# interface_th.net
KiCad netlist of a schematic drawn in EAGLE
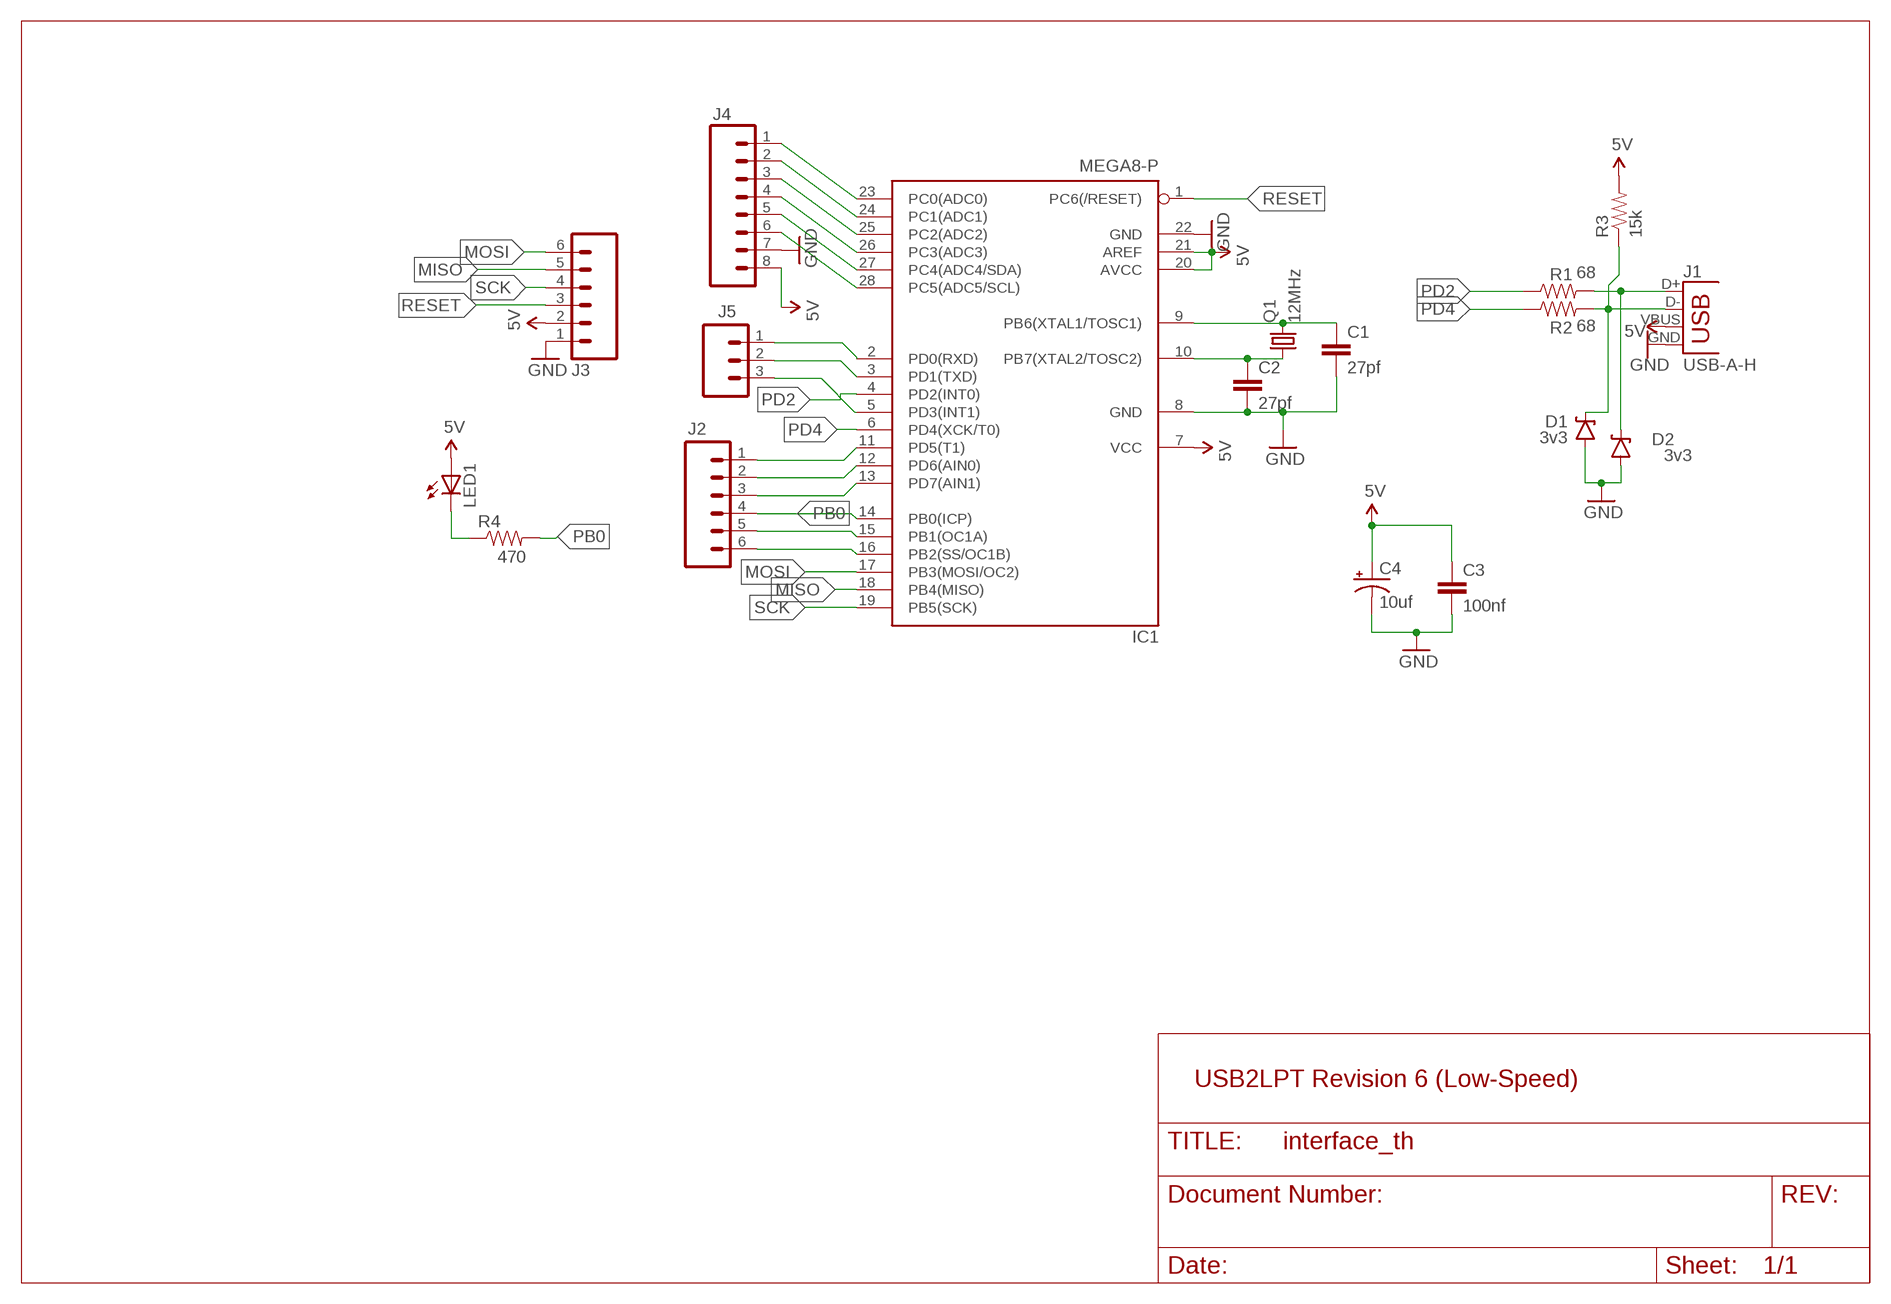
[diagram p0: schematic, sheet 1]

(export (version "E")
  (design (tool "Eeschema 10.0.6"))
  (components
    (comp (ref "C1")
      (value "27pf")
      (footprint "eagle-import:CAP-PTH-SMALL")
      (libsource (lib "eagle-import") (part "SparkFun-Passives_CAPPTH"))
    )
    (comp (ref "C2")
      (value "27pf")
      (footprint "eagle-import:CAP-PTH-SMALL")
      (libsource (lib "eagle-import") (part "SparkFun-Passives_CAPPTH"))
    )
    (comp (ref "C3")
      (value "100nf")
      (footprint "eagle-import:CAP-PTH-SMALL")
      (libsource (lib "eagle-import") (part "CAPPTH"))
    )
    (comp (ref "C4")
      (value "10uf")
      (footprint "eagle-import:CPOL-RADIAL-10UF-25V")
      (libsource (lib "eagle-import") (part "CAP_POLPTH2"))
    )
    (comp (ref "D1")
      (value "3v3")
      (footprint "eagle-import:DIODE-BZT52")
      (libsource (lib "eagle-import") (part "DIODE-ZENER"))
    )
    (comp (ref "D2")
      (value "3v3")
      (footprint "eagle-import:DIODE-BZT52")
      (libsource (lib "eagle-import") (part "DIODE-ZENER"))
    )
    (comp (ref "IC1")
      (value "MEGA8-P")
      (footprint "eagle-import:DIL28-3")
      (libsource (lib "eagle-import") (part "MEGA8-P"))
    )
    (comp (ref "J1")
      (value "USB-A-H")
      (footprint "eagle-import:USB-A-H")
      (libsource (lib "eagle-import") (part "USB-A-H"))
    )
    (comp (ref "J2")
      (value "M06LONGPADS")
      (footprint "eagle-import:1X06_LONGPADS")
      (libsource (lib "eagle-import") (part "M06LONGPADS"))
    )
    (comp (ref "J3")
      (value "M06LONGPADS")
      (footprint "eagle-import:1X06_LONGPADS")
      (libsource (lib "eagle-import") (part "M06LONGPADS"))
    )
    (comp (ref "J4")
      (value "M08LONGPADS")
      (footprint "eagle-import:1X08_LONGPADS")
      (libsource (lib "eagle-import") (part "M08LONGPADS"))
    )
    (comp (ref "J5")
      (value "M03LONGPADS")
      (footprint "eagle-import:1X03_LONGPADS")
      (libsource (lib "eagle-import") (part "M03LONGPADS"))
    )
    (comp (ref "LED1")
      (value "LED3MM")
      (footprint "eagle-import:LED3MM")
      (libsource (lib "eagle-import") (part "LED3MM"))
    )
    (comp (ref "Q1")
      (value "12MHz")
      (footprint "eagle-import:HC49U-V")
      (libsource (lib "eagle-import") (part "CRYSTALHC49U-V"))
    )
    (comp (ref "R1")
      (value "68")
      (footprint "eagle-import:AXIAL-0.3")
      (libsource (lib "eagle-import") (part "RESISTORAXIAL-0.3"))
    )
    (comp (ref "R2")
      (value "68")
      (footprint "eagle-import:AXIAL-0.3")
      (libsource (lib "eagle-import") (part "RESISTORAXIAL-0.3"))
    )
    (comp (ref "R3")
      (value "15k")
      (footprint "eagle-import:AXIAL-0.3")
      (libsource (lib "eagle-import") (part "RESISTORAXIAL-0.3"))
    )
    (comp (ref "R4")
      (value "470")
      (footprint "eagle-import:AXIAL-0.3")
      (libsource (lib "eagle-import") (part "RESISTORAXIAL-0.3"))
    )
  )
  (nets
    (net (code "1") (name "5V") (class "Default")
      (node (ref "C3") (pin "1") (pinfunction "1_1") (pintype "passive"))
      (node (ref "C4") (pin "1") (pinfunction "+_1") (pintype "passive"))
      (node (ref "IC1") (pin "20") (pinfunction "AVCC_20") (pintype "power_in"))
      (node (ref "IC1") (pin "21") (pinfunction "AREF_21") (pintype "passive"))
      (node (ref "IC1") (pin "7") (pinfunction "VCC_7") (pintype "power_in"))
      (node (ref "J1") (pin "VBUS") (pinfunction "VBUS_VBUS") (pintype "bidirectional"))
      (node (ref "J3") (pin "2") (pinfunction "2_2") (pintype "passive"))
      (node (ref "J4") (pin "8") (pinfunction "8_8") (pintype "passive"))
      (node (ref "LED1") (pin "A") (pinfunction "A_A") (pintype "passive"))
      (node (ref "R3") (pin "P$2") (pinfunction "2_P$2") (pintype "passive"))
    )
    (net (code "2") (name "GND") (class "Default")
      (node (ref "C1") (pin "2") (pinfunction "2_2") (pintype "passive"))
      (node (ref "C2") (pin "2") (pinfunction "2_2") (pintype "passive"))
      (node (ref "C3") (pin "2") (pinfunction "2_2") (pintype "passive"))
      (node (ref "C4") (pin "2") (pinfunction "-_2") (pintype "passive"))
      (node (ref "D1") (pin "A") (pinfunction "A_A") (pintype "passive"))
      (node (ref "D2") (pin "A") (pinfunction "A_A") (pintype "passive"))
      (node (ref "IC1") (pin "22") (pinfunction "GND_22") (pintype "power_in"))
      (node (ref "IC1") (pin "8") (pinfunction "GND_8") (pintype "power_in"))
      (node (ref "J1") (pin "GND") (pinfunction "GND_GND") (pintype "bidirectional"))
      (node (ref "J3") (pin "1") (pinfunction "1_1") (pintype "passive"))
      (node (ref "J4") (pin "7") (pinfunction "7_7") (pintype "passive"))
    )
    (net (code "3") (name "MISO") (class "Default")
      (node (ref "IC1") (pin "18") (pinfunction "PB4(MISO)_18") (pintype "bidirectional"))
      (node (ref "J3") (pin "5") (pinfunction "5_5") (pintype "passive"))
    )
    (net (code "4") (name "MOSI") (class "Default")
      (node (ref "IC1") (pin "17") (pinfunction "PB3(MOSI/OC2)_17") (pintype "bidirectional"))
      (node (ref "J3") (pin "6") (pinfunction "6_6") (pintype "passive"))
    )
    (net (code "5") (name "Net-(IC1-PB1(OC1A))") (class "Default")
      (node (ref "IC1") (pin "15") (pinfunction "PB1(OC1A)_15") (pintype "bidirectional"))
      (node (ref "J2") (pin "5") (pinfunction "5_5") (pintype "passive"))
    )
    (net (code "6") (name "Net-(IC1-PB2(SS{slash}OC1B))") (class "Default")
      (node (ref "IC1") (pin "16") (pinfunction "PB2(SS/OC1B)_16") (pintype "bidirectional"))
      (node (ref "J2") (pin "6") (pinfunction "6_6") (pintype "passive"))
    )
    (net (code "7") (name "Net-(IC1-PB6(XTAL1{slash}TOSC1))") (class "Default")
      (node (ref "C1") (pin "1") (pinfunction "1_1") (pintype "passive"))
      (node (ref "IC1") (pin "9") (pinfunction "PB6(XTAL1/TOSC1)_9") (pintype "bidirectional"))
      (node (ref "Q1") (pin "2") (pinfunction "2_2") (pintype "passive"))
    )
    (net (code "8") (name "Net-(IC1-PB7(XTAL2{slash}TOSC2))") (class "Default")
      (node (ref "C2") (pin "1") (pinfunction "1_1") (pintype "passive"))
      (node (ref "IC1") (pin "10") (pinfunction "PB7(XTAL2/TOSC2)_10") (pintype "bidirectional"))
      (node (ref "Q1") (pin "1") (pinfunction "1_1") (pintype "passive"))
    )
    (net (code "9") (name "Net-(IC1-PC0(ADC0))") (class "Default")
      (node (ref "IC1") (pin "23") (pinfunction "PC0(ADC0)_23") (pintype "bidirectional"))
      (node (ref "J4") (pin "1") (pinfunction "1_1") (pintype "passive"))
    )
    (net (code "10") (name "Net-(IC1-PC1(ADC1))") (class "Default")
      (node (ref "IC1") (pin "24") (pinfunction "PC1(ADC1)_24") (pintype "bidirectional"))
      (node (ref "J4") (pin "2") (pinfunction "2_2") (pintype "passive"))
    )
    (net (code "11") (name "Net-(IC1-PC2(ADC2))") (class "Default")
      (node (ref "IC1") (pin "25") (pinfunction "PC2(ADC2)_25") (pintype "bidirectional"))
      (node (ref "J4") (pin "3") (pinfunction "3_3") (pintype "passive"))
    )
    (net (code "12") (name "Net-(IC1-PC3(ADC3))") (class "Default")
      (node (ref "IC1") (pin "26") (pinfunction "PC3(ADC3)_26") (pintype "bidirectional"))
      (node (ref "J4") (pin "4") (pinfunction "4_4") (pintype "passive"))
    )
    (net (code "13") (name "Net-(IC1-PC4(ADC4{slash}SDA))") (class "Default")
      (node (ref "IC1") (pin "27") (pinfunction "PC4(ADC4/SDA)_27") (pintype "bidirectional"))
      (node (ref "J4") (pin "5") (pinfunction "5_5") (pintype "passive"))
    )
    (net (code "14") (name "Net-(IC1-PC5(ADC5{slash}SCL))") (class "Default")
      (node (ref "IC1") (pin "28") (pinfunction "PC5(ADC5/SCL)_28") (pintype "bidirectional"))
      (node (ref "J4") (pin "6") (pinfunction "6_6") (pintype "passive"))
    )
    (net (code "15") (name "Net-(IC1-PD0(RXD))") (class "Default")
      (node (ref "IC1") (pin "2") (pinfunction "PD0(RXD)_2") (pintype "bidirectional"))
      (node (ref "J5") (pin "1") (pinfunction "1_1") (pintype "passive"))
    )
    (net (code "16") (name "Net-(IC1-PD1(TXD))") (class "Default")
      (node (ref "IC1") (pin "3") (pinfunction "PD1(TXD)_3") (pintype "bidirectional"))
      (node (ref "J5") (pin "2") (pinfunction "2_2") (pintype "passive"))
    )
    (net (code "17") (name "Net-(IC1-PD3(INT1))") (class "Default")
      (node (ref "IC1") (pin "5") (pinfunction "PD3(INT1)_5") (pintype "bidirectional"))
      (node (ref "J5") (pin "3") (pinfunction "3_3") (pintype "passive"))
    )
    (net (code "18") (name "Net-(IC1-PD5(T1))") (class "Default")
      (node (ref "IC1") (pin "11") (pinfunction "PD5(T1)_11") (pintype "bidirectional"))
      (node (ref "J2") (pin "1") (pinfunction "1_1") (pintype "passive"))
    )
    (net (code "19") (name "Net-(IC1-PD6(AIN0))") (class "Default")
      (node (ref "IC1") (pin "12") (pinfunction "PD6(AIN0)_12") (pintype "bidirectional"))
      (node (ref "J2") (pin "2") (pinfunction "2_2") (pintype "passive"))
    )
    (net (code "20") (name "Net-(IC1-PD7(AIN1))") (class "Default")
      (node (ref "IC1") (pin "13") (pinfunction "PD7(AIN1)_13") (pintype "bidirectional"))
      (node (ref "J2") (pin "3") (pinfunction "3_3") (pintype "passive"))
    )
    (net (code "21") (name "Net-(LED1-C)") (class "Default")
      (node (ref "LED1") (pin "K") (pinfunction "C_K") (pintype "passive"))
      (node (ref "R4") (pin "P$1") (pinfunction "1_P$1") (pintype "passive"))
    )
    (net (code "22") (name "Net-(R1-2)") (class "Default")
      (node (ref "D2") (pin "C") (pinfunction "C_C") (pintype "passive"))
      (node (ref "J1") (pin "D+") (pinfunction "D+_D+") (pintype "bidirectional"))
      (node (ref "R1") (pin "P$2") (pinfunction "2_P$2") (pintype "passive"))
    )
    (net (code "23") (name "Net-(R2-2)") (class "Default")
      (node (ref "D1") (pin "C") (pinfunction "C_C") (pintype "passive"))
      (node (ref "J1") (pin "D-") (pinfunction "D-_D-") (pintype "bidirectional"))
      (node (ref "R2") (pin "P$2") (pinfunction "2_P$2") (pintype "passive"))
      (node (ref "R3") (pin "P$1") (pinfunction "1_P$1") (pintype "passive"))
    )
    (net (code "24") (name "PB0") (class "Default")
      (node (ref "IC1") (pin "14") (pinfunction "PB0(ICP)_14") (pintype "bidirectional"))
      (node (ref "J2") (pin "4") (pinfunction "4_4") (pintype "passive"))
      (node (ref "R4") (pin "P$2") (pinfunction "2_P$2") (pintype "passive"))
    )
    (net (code "25") (name "PD2") (class "Default")
      (node (ref "IC1") (pin "4") (pinfunction "PD2(INT0)_4") (pintype "bidirectional"))
      (node (ref "R1") (pin "P$1") (pinfunction "1_P$1") (pintype "passive"))
    )
    (net (code "26") (name "PD4") (class "Default")
      (node (ref "IC1") (pin "6") (pinfunction "PD4(XCK/T0)_6") (pintype "bidirectional"))
      (node (ref "R2") (pin "P$1") (pinfunction "1_P$1") (pintype "passive"))
    )
    (net (code "27") (name "RESET") (class "Default")
      (node (ref "IC1") (pin "1") (pinfunction "PC6(/RESET)_1") (pintype "bidirectional"))
      (node (ref "J3") (pin "3") (pinfunction "3_3") (pintype "passive"))
    )
    (net (code "28") (name "SCK") (class "Default")
      (node (ref "IC1") (pin "19") (pinfunction "PB5(SCK)_19") (pintype "bidirectional"))
      (node (ref "J3") (pin "4") (pinfunction "4_4") (pintype "passive"))
    )
  )
)
